# 3_3V_Converter.net
KiCad netlist of a schematic drawn in Altium Designer
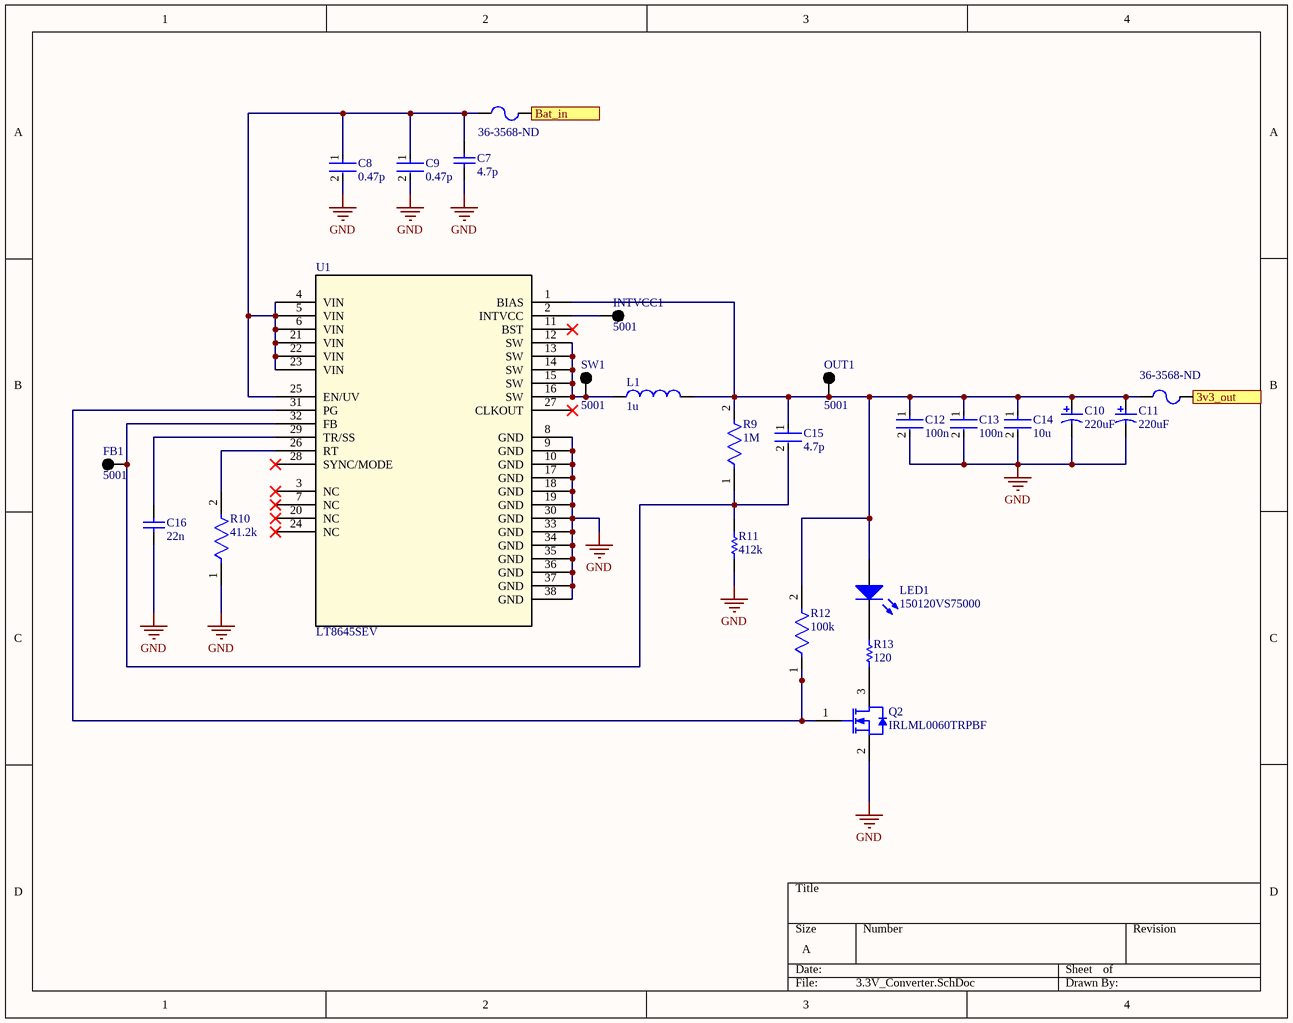
[diagram p0: 3.3V_Converter.SchDoc]

(export (version "E")
  (design (tool "Eeschema 10.0.6"))
  (components
    (comp (ref "C7")
      (value "4.7p")
      (footprint "CAPC1608X90X35ML10T15")
      (fields (field (name "PART NUMBER") "GRM1885C1H4R7CA01D") (field (name "MANUFACTURER") "Murata"))
      (libsource (lib "Altium Content Vault") (part "CAP"))
    )
    (comp (ref "C8")
      (value "0.47p")
      (footprint "FP-CL21-IPC_B")
      (description "CL21 Series 0805 0.47pF 50V ±0.1pF Tolerance C0G Multilayer Ceramic Chip Capacitor")
      (fields (field (name "VOLTAGE") "50V"))
      (libsource (lib "Altium Content Vault") (part "b4654b650e69147ec39a6b967a45e02"))
    )
    (comp (ref "C9")
      (value "0.47p")
      (footprint "FP-CL21-IPC_B")
      (description "CL21 Series 0805 0.47pF 50V ±0.1pF Tolerance C0G Multilayer Ceramic Chip Capacitor")
      (fields (field (name "VOLTAGE") "50V"))
      (libsource (lib "Altium Content Vault") (part "b4654b650e69147ec39a6b967a45e02"))
    )
    (comp (ref "C10")
      (value "220uF")
      (footprint "CAPPR65-500-1250X1000X1350")
      (description "Aluminum Electrolytic Capacitor, 220 uF, +/- 20%, 50 V, -40 to 85 degC, 2-Pin THD, RoHS, Bulk")
      (libsource (lib "Altium Content Vault") (part "CAP-P-2"))
    )
    (comp (ref "C11")
      (value "220uF")
      (footprint "CAPPR65-500-1250X1000X1350")
      (description "Aluminum Electrolytic Capacitor, 220 uF, +/- 20%, 50 V, -40 to 85 degC, 2-Pin THD, RoHS, Bulk")
      (libsource (lib "Altium Content Vault") (part "CAP-P-2"))
    )
    (comp (ref "C12")
      (value "100n")
      (footprint "FP-CL10-IPC_A")
      (description "Cap Ceramic 100nF 50V X7R ±10% Pad SMD 0603 +125°C T/R")
      (fields (field (name "VOLTAGE") "50V") (field (name "TOLERANCE") "10%"))
      (libsource (lib "Altium Content Vault") (part "b4654b650e69147ec39a6b967a45e02"))
    )
    (comp (ref "C13")
      (value "100n")
      (footprint "FP-CL10-IPC_A")
      (description "Cap Ceramic 100nF 50V X7R ±10% Pad SMD 0603 +125°C T/R")
      (fields (field (name "VOLTAGE") "50V") (field (name "TOLERANCE") "10%"))
      (libsource (lib "Altium Content Vault") (part "b4654b650e69147ec39a6b967a45e02"))
    )
    (comp (ref "C14")
      (value "10u")
      (footprint "FP-GRM21B-0_15-IPC_C")
      (description "Chip Multilayer Ceramic Capacitors for General Purpose, 0805, 10uF, X5R, 15%, 10%, 25V")
      (fields (field (name "VOLTAGE") "25V") (field (name "TOLERANCE") "10%"))
      (libsource (lib "Altium Content Vault") (part "b4654b650e69147ec39a6b967a45e02"))
    )
    (comp (ref "C15")
      (value "4.7p")
      (footprint "FP-0603-L_1_6_0_15-W_0_81-MFG")
      (description "General Purpose Ceramic Capacitor, 0603, 4.7pF, 0.25pF, NP0, 30ppm/°C, 50V")
      (libsource (lib "Altium Content Vault") (part "02cd4be3c70576c341d710602a673aa"))
    )
    (comp (ref "C16")
      (value "22n")
      (footprint "CAPC1608X90X35ML10T15")
      (fields (field (name "MANUFACTURER") "Murata") (field (name "PART NUMBER") "GRM188R71H223KA01D"))
      (libsource (lib "Altium Content Vault") (part "CAP"))
    )
    (comp (ref "F1")
      (value "36-3568-ND")
      (footprint "PCBComponent_1")
      (libsource (lib "3568FuseHolder1") (part "Fuse_Holder"))
    )
    (comp (ref "F2")
      (value "36-3568-ND")
      (footprint "PCBComponent_1")
      (libsource (lib "3568FuseHolder1") (part "Fuse_Holder"))
    )
    (comp (ref "FB1")
      (value "5001")
      (footprint "KSTN-5001")
      (description "Test Point, Black, 1-Pin THD, RoHS, Bulk")
      (fields (field (name "MANUFACTURER") "Keystone"))
      (libsource (lib "Altium Content Vault") (part "KSTN-TP-5001"))
    )
    (comp (ref "INTVCC1")
      (value "5001")
      (footprint "KSTN-5001")
      (description "Test Point, Black, 1-Pin THD, RoHS, Bulk")
      (fields (field (name "MANUFACTURER") "Keystone"))
      (libsource (lib "Altium Content Vault") (part "KSTN-TP-5001"))
    )
    (comp (ref "L1")
      (value "1u")
      (footprint "PCBComponent_1")
      (libsource (lib "XAL6030-102MEC") (part "XAL6030-102MEC"))
    )
    (comp (ref "LED1")
      (value "150120VS75000")
      (footprint "1206_A")
      (description "SMD mono-color Chip LED, WL-SMCW, Bright Green")
      (fields (field (name "MANUFACTURER") "Wuerth Elektronik"))
      (libsource (lib "Altium Content Vault") (part "WE-LED_K1A2-2"))
    )
    (comp (ref "OUT1")
      (value "5001")
      (footprint "KSTN-5001")
      (description "Test Point, Black, 1-Pin THD, RoHS, Bulk")
      (fields (field (name "MANUFACTURER") "Keystone"))
      (libsource (lib "Altium Content Vault") (part "KSTN-TP-5001"))
    )
    (comp (ref "Q2")
      (value "IRLML0060TRPBF")
      (footprint "INTR-SOT-23-3_V")
      (description "HEXFET Power MOSFET\r\n, 60 V, 2.7 A, -55 to 150 degC, 3-Pin SOT-23, RoHS, Tape and Reel")
      (fields (field (name "MANUFACTURER") "International Rectifier"))
      (libsource (lib "Altium Content Vault") (part "NEMOS-GSD-3"))
    )
    (comp (ref "R9")
      (value "1M")
      (footprint "FP-CRCW0603-e3-MFG")
      (description "RES Thick Film, 1MΩ, 1%, 0.1W, 100ppm/°C, 0603")
      (fields (field (name "TOLERANCE") "1%"))
      (libsource (lib "Altium Content Vault") (part "1029c3af85768c4190bb7ad29bc67b5"))
    )
    (comp (ref "R10")
      (value "41.2k")
      (footprint "FP-CRCW0603-e3-MFG")
      (description "RES Thick Film, 41.2kΩ, 1%, 0.1W, 100ppm/°C, 0603")
      (fields (field (name "TOLERANCE") "1%"))
      (libsource (lib "Altium Content Vault") (part "1029c3af85768c4190bb7ad29bc67b5"))
    )
    (comp (ref "R11")
      (value "412k")
      (footprint "RESC1608X55X30LL15T15")
      (fields (field (name "MANUFACTURER") "Panasonic") (field (name "PART NUMBER") "ERJ-3EKF4123V"))
      (libsource (lib "Altium Content Vault") (part "RES"))
    )
    (comp (ref "R12")
      (value "100k")
      (footprint "FP-RC0603-0_55-MFG")
      (description "RES SMD 100K OHM 1% 1/10W 0603")
      (fields (field (name "TOLERANCE") "1%"))
      (libsource (lib "Altium Content Vault") (part "1029c3af85768c4190bb7ad29bc67b5"))
    )
    (comp (ref "R13")
      (value "120")
      (footprint "RESC1609X55X30ML15T15")
      (description "Chip Resistor, 120 Ohm, +/- 1%, 0.1 W, -55 to 155 degC, 0603 (1608 Metric), RoHS, Tape and Reel")
      (fields (field (name "TOLERANCE") "1%") (field (name "MANUFACTURER") "Panasonic"))
      (libsource (lib "Altium Content Vault") (part "RES-2"))
    )
    (comp (ref "SW1")
      (value "5001")
      (footprint "KSTN-5001")
      (description "Test Point, Black, 1-Pin THD, RoHS, Bulk")
      (fields (field (name "MANUFACTURER") "Keystone"))
      (libsource (lib "Altium Content Vault") (part "KSTN-TP-5001"))
    )
    (comp (ref "U1")
      (value "LT8645SEV")
      (footprint "LQFN-32")
      (description "No Description Available")
      (fields (field (name "COPYRIGHT") "Copyright (C) 2018 Accelerated Designs. All rights reserved"))
      (libsource (lib "LT8645S_Library") (part "LT8645SEV"))
    )
  )
  (nets
    (net (code "1") (name "/3v3_out") (class "Default")
      (node (ref "F2") (pin "2") (pinfunction "2_2") (pintype "passive"))
    )
    (net (code "2") (name "/Bat_in") (class "Default")
      (node (ref "F1") (pin "2") (pinfunction "2_2") (pintype "passive"))
    )
    (net (code "3") (name "GND") (class "Default")
      (node (ref "C10") (pin "2") (pinfunction "2_2") (pintype "passive"))
      (node (ref "C11") (pin "2") (pinfunction "2_2") (pintype "passive"))
      (node (ref "C12") (pin "2") (pinfunction "2_2") (pintype "passive"))
      (node (ref "C13") (pin "2") (pinfunction "2_2") (pintype "passive"))
      (node (ref "C14") (pin "2") (pinfunction "2_2") (pintype "passive"))
      (node (ref "C16") (pin "1") (pinfunction "1_1") (pintype "passive"))
      (node (ref "C7") (pin "1") (pinfunction "1_1") (pintype "passive"))
      (node (ref "C8") (pin "2") (pinfunction "2_2") (pintype "passive"))
      (node (ref "C9") (pin "2") (pinfunction "2_2") (pintype "passive"))
      (node (ref "Q2") (pin "2") (pinfunction "S_2") (pintype "passive"))
      (node (ref "R10") (pin "1") (pinfunction "1_1") (pintype "passive"))
      (node (ref "R11") (pin "1") (pinfunction "1_1") (pintype "passive"))
      (node (ref "U1") (pin "10") (pinfunction "GND_10") (pintype "passive"))
      (node (ref "U1") (pin "17") (pinfunction "GND_17") (pintype "passive"))
      (node (ref "U1") (pin "18") (pinfunction "GND_18") (pintype "passive"))
      (node (ref "U1") (pin "19") (pinfunction "GND_19") (pintype "passive"))
      (node (ref "U1") (pin "30") (pinfunction "GND_30") (pintype "passive"))
      (node (ref "U1") (pin "33") (pinfunction "GND_33") (pintype "passive"))
      (node (ref "U1") (pin "34") (pinfunction "GND_34") (pintype "passive"))
      (node (ref "U1") (pin "35") (pinfunction "GND_35") (pintype "passive"))
      (node (ref "U1") (pin "36") (pinfunction "GND_36") (pintype "passive"))
      (node (ref "U1") (pin "37") (pinfunction "GND_37") (pintype "passive"))
      (node (ref "U1") (pin "38") (pinfunction "GND_38") (pintype "passive"))
      (node (ref "U1") (pin "8") (pinfunction "GND_8") (pintype "passive"))
      (node (ref "U1") (pin "9") (pinfunction "GND_9") (pintype "passive"))
    )
    (net (code "4") (name "Net-(L1-Pad1)") (class "Default")
      (node (ref "L1") (pin "1") (pinfunction "1_1") (pintype "passive"))
      (node (ref "SW1") (pin "1") (pintype "passive"))
      (node (ref "U1") (pin "12") (pinfunction "SW_12") (pintype "passive"))
      (node (ref "U1") (pin "13") (pinfunction "SW_13") (pintype "passive"))
      (node (ref "U1") (pin "14") (pinfunction "SW_14") (pintype "passive"))
      (node (ref "U1") (pin "15") (pinfunction "SW_15") (pintype "passive"))
      (node (ref "U1") (pin "16") (pinfunction "SW_16") (pintype "passive"))
    )
    (net (code "5") (name "Net-(LED1-A)") (class "Default")
      (node (ref "C10") (pin "1") (pinfunction "1_1") (pintype "passive"))
      (node (ref "C11") (pin "1") (pinfunction "1_1") (pintype "passive"))
      (node (ref "C12") (pin "1") (pinfunction "1_1") (pintype "passive"))
      (node (ref "C13") (pin "1") (pinfunction "1_1") (pintype "passive"))
      (node (ref "C14") (pin "1") (pinfunction "1_1") (pintype "passive"))
      (node (ref "C15") (pin "1") (pinfunction "1_1") (pintype "passive"))
      (node (ref "F2") (pin "1") (pinfunction "1_1") (pintype "passive"))
      (node (ref "L1") (pin "2") (pinfunction "2_2") (pintype "passive"))
      (node (ref "LED1") (pin "2") (pinfunction "A_2") (pintype "passive"))
      (node (ref "OUT1") (pin "1") (pintype "passive"))
      (node (ref "R12") (pin "2") (pinfunction "2_2") (pintype "passive"))
      (node (ref "R9") (pin "2") (pinfunction "2_2") (pintype "passive"))
      (node (ref "U1") (pin "1") (pinfunction "BIAS_1") (pintype "passive"))
    )
    (net (code "6") (name "Net-(LED1-K)") (class "Default")
      (node (ref "LED1") (pin "1") (pinfunction "K_1") (pintype "passive"))
      (node (ref "R13") (pin "2") (pinfunction "2_2") (pintype "passive"))
    )
    (net (code "7") (name "Net-(Q2-D)") (class "Default")
      (node (ref "Q2") (pin "3") (pinfunction "D_3") (pintype "passive"))
      (node (ref "R13") (pin "1") (pinfunction "1_1") (pintype "passive"))
    )
    (net (code "8") (name "Net-(Q2-G)") (class "Default")
      (node (ref "Q2") (pin "1") (pinfunction "G_1") (pintype "passive"))
      (node (ref "R12") (pin "1") (pinfunction "1_1") (pintype "passive"))
      (node (ref "U1") (pin "31") (pinfunction "PG_31") (pintype "passive"))
    )
    (net (code "9") (name "Net-(U1-EN{slash}UV)") (class "Default")
      (node (ref "C7") (pin "2") (pinfunction "2_2") (pintype "passive"))
      (node (ref "C8") (pin "1") (pinfunction "1_1") (pintype "passive"))
      (node (ref "C9") (pin "1") (pinfunction "1_1") (pintype "passive"))
      (node (ref "F1") (pin "1") (pinfunction "1_1") (pintype "passive"))
      (node (ref "U1") (pin "21") (pinfunction "VIN_21") (pintype "passive"))
      (node (ref "U1") (pin "22") (pinfunction "VIN_22") (pintype "passive"))
      (node (ref "U1") (pin "23") (pinfunction "VIN_23") (pintype "passive"))
      (node (ref "U1") (pin "25") (pinfunction "EN/UV_25") (pintype "passive"))
      (node (ref "U1") (pin "4") (pinfunction "VIN_4") (pintype "passive"))
      (node (ref "U1") (pin "5") (pinfunction "VIN_5") (pintype "passive"))
      (node (ref "U1") (pin "6") (pinfunction "VIN_6") (pintype "passive"))
    )
    (net (code "10") (name "Net-(U1-FB)") (class "Default")
      (node (ref "C15") (pin "2") (pinfunction "2_2") (pintype "passive"))
      (node (ref "FB1") (pin "1") (pintype "passive"))
      (node (ref "R11") (pin "2") (pinfunction "2_2") (pintype "passive"))
      (node (ref "R9") (pin "1") (pinfunction "1_1") (pintype "passive"))
      (node (ref "U1") (pin "32") (pinfunction "FB_32") (pintype "passive"))
    )
    (net (code "11") (name "Net-(U1-INTVCC)") (class "Default")
      (node (ref "INTVCC1") (pin "1") (pintype "passive"))
      (node (ref "U1") (pin "2") (pinfunction "INTVCC_2") (pintype "passive"))
    )
    (net (code "12") (name "Net-(U1-RT)") (class "Default")
      (node (ref "R10") (pin "2") (pinfunction "2_2") (pintype "passive"))
      (node (ref "U1") (pin "26") (pinfunction "RT_26") (pintype "passive"))
    )
    (net (code "13") (name "Net-(U1-TR{slash}SS)") (class "Default")
      (node (ref "C16") (pin "2") (pinfunction "2_2") (pintype "passive"))
      (node (ref "U1") (pin "29") (pinfunction "TR/SS_29") (pintype "passive"))
    )
    (net (code "14") (name "unconnected-(U1-BST-Pad11)") (class "Default")
      (node (ref "U1") (pin "11") (pinfunction "BST_11") (pintype "passive+no_connect"))
    )
    (net (code "15") (name "unconnected-(U1-CLKOUT-Pad27)") (class "Default")
      (node (ref "U1") (pin "27") (pinfunction "CLKOUT_27") (pintype "passive+no_connect"))
    )
    (net (code "16") (name "unconnected-(U1-NC-Pad3)") (class "Default")
      (node (ref "U1") (pin "3") (pinfunction "NC_3") (pintype "passive+no_connect"))
    )
    (net (code "17") (name "unconnected-(U1-NC-Pad7)") (class "Default")
      (node (ref "U1") (pin "7") (pinfunction "NC_7") (pintype "passive+no_connect"))
    )
    (net (code "18") (name "unconnected-(U1-NC-Pad20)") (class "Default")
      (node (ref "U1") (pin "20") (pinfunction "NC_20") (pintype "passive+no_connect"))
    )
    (net (code "19") (name "unconnected-(U1-NC-Pad24)") (class "Default")
      (node (ref "U1") (pin "24") (pinfunction "NC_24") (pintype "passive+no_connect"))
    )
    (net (code "20") (name "unconnected-(U1-SYNC{slash}MODE-Pad28)") (class "Default")
      (node (ref "U1") (pin "28") (pinfunction "SYNC/MODE_28") (pintype "passive+no_connect"))
    )
  )
)
